# V4-AddRS485-V01-017.net
KiCad netlist of a schematic drawn in EAGLE
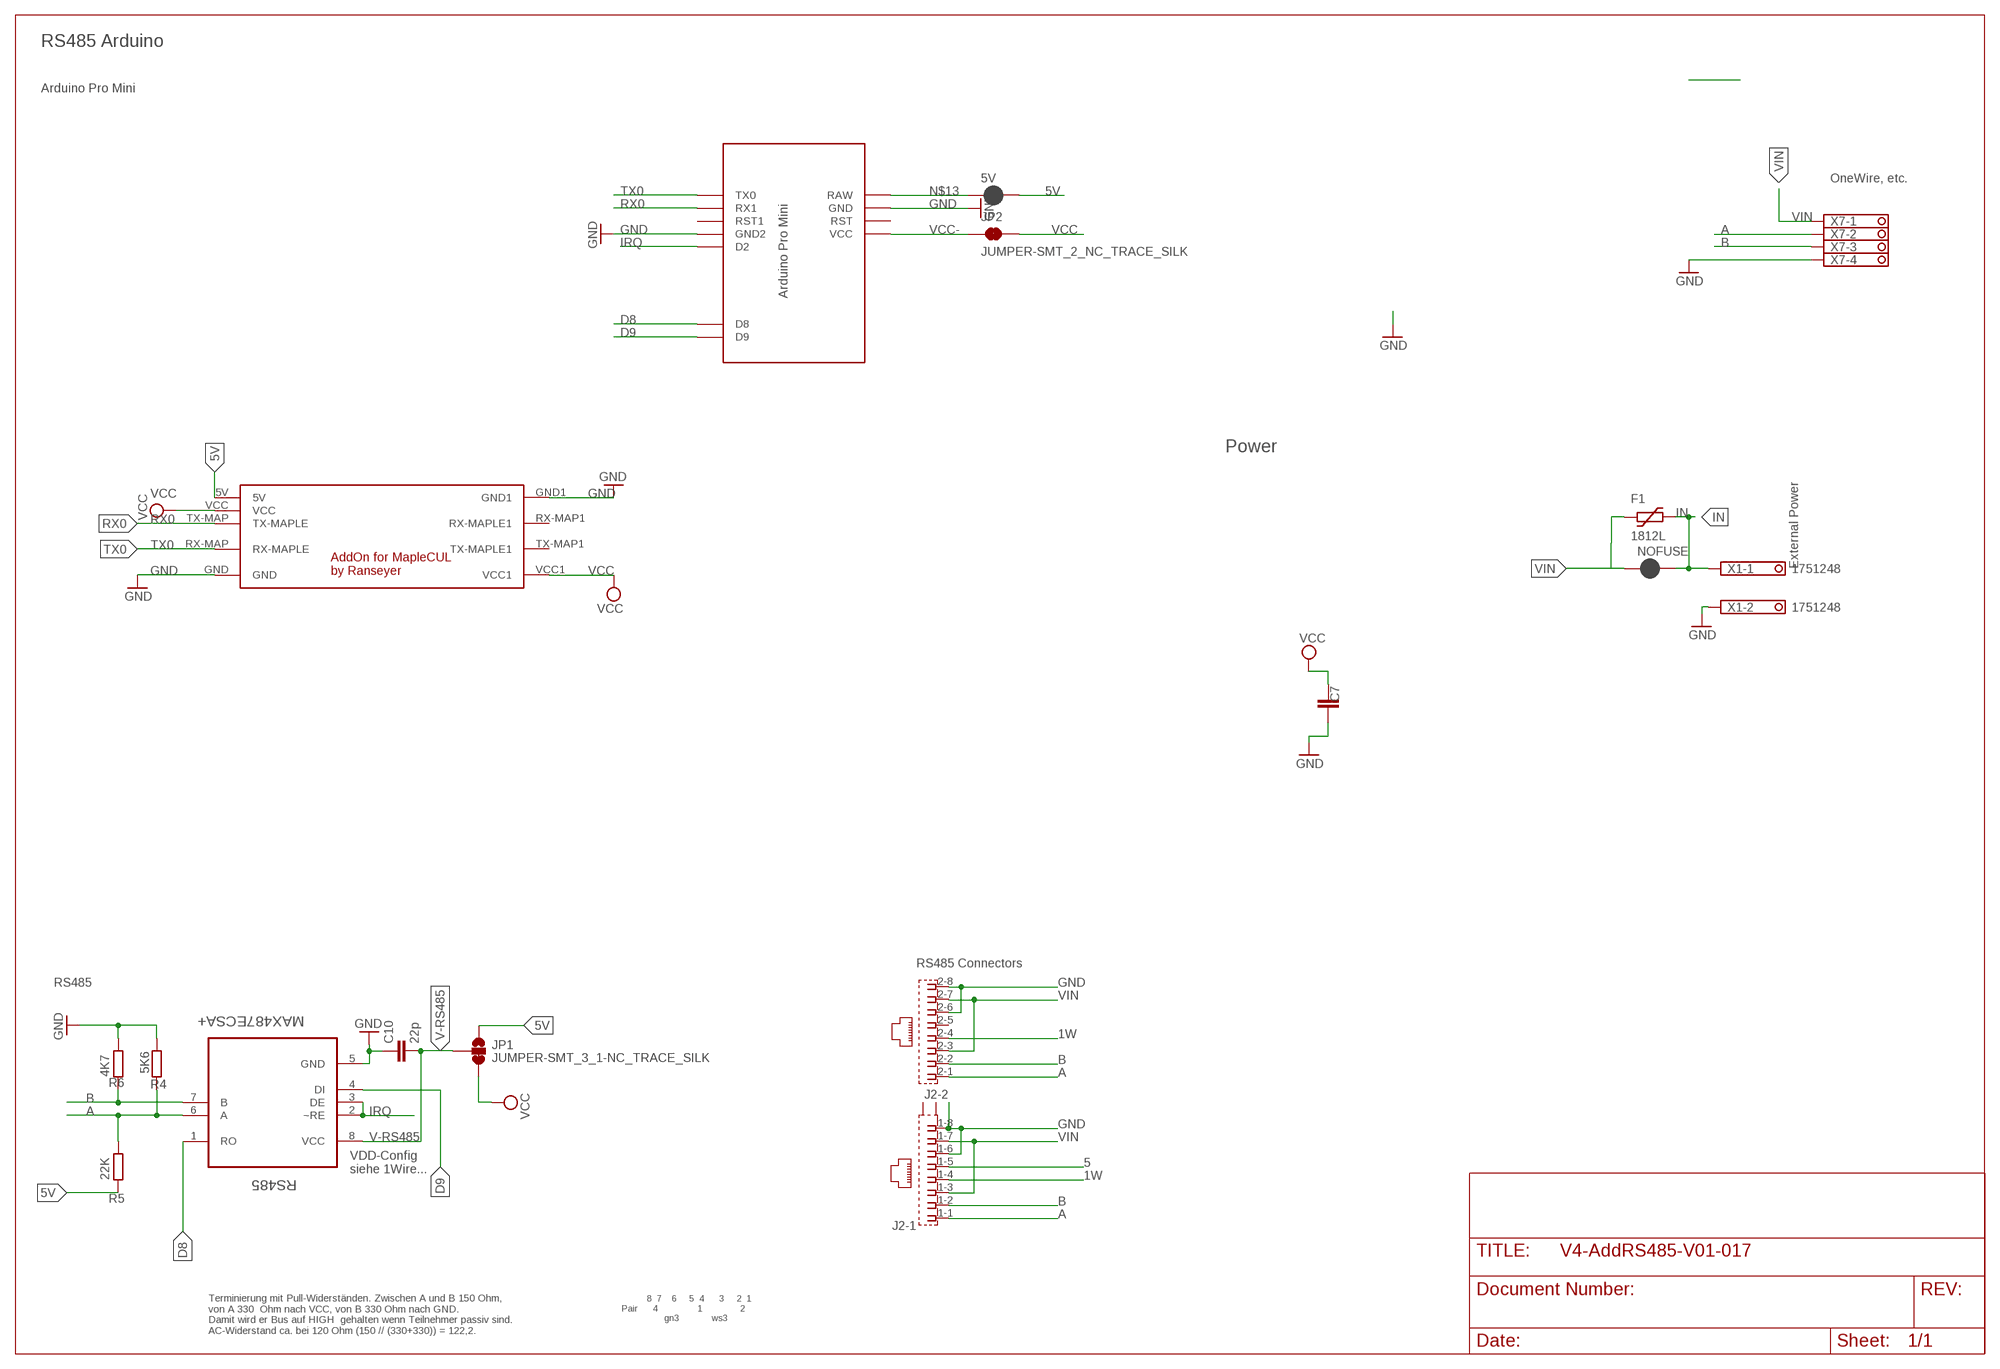
[diagram p0: schematic, sheet 1]

(export (version "E")
  (design (tool "Eeschema 10.0.6"))
  (components
    (comp (ref "5V")
      (value "JUMPER-SMT_2_NC_PASTE_NO-SILK")
      (footprint "eagle-import:SMT-JUMPER_2_NC_PASTE_NO-SILK")
      (libsource (lib "eagle-import") (part "JUMPER-SMT_2_NC_PASTE_NO-SILK"))
    )
    (comp (ref "C7")
      (value "C-EUC1812")
      (footprint "eagle-import:C1812")
      (libsource (lib "eagle-import") (part "rcl_334_C-EUC1812"))
    )
    (comp (ref "C10")
      (value "22p")
      (footprint "eagle-import:C0805")
      (libsource (lib "eagle-import") (part "C-EUC0805"))
    )
    (comp (ref "F1")
      (value "1812L")
      (footprint "eagle-import:1812L")
      (libsource (lib "eagle-import") (part "1812L"))
    )
    (comp (ref "J2")
      (value "RJ45_2X_S")
      (footprint "eagle-import:RJ45_2X_S")
      (libsource (lib "eagle-import") (part "RJ45_2X_S"))
    )
    (comp (ref "JP1")
      (value "JUMPER-SMT_3_1-NC_TRACE_SILK")
      (footprint "eagle-import:SMT-JUMPER_3_1-NC_TRACE_SILK")
      (libsource (lib "eagle-import") (part "JUMPER-SMT_3_1-NC_TRACE_SILK"))
    )
    (comp (ref "JP2")
      (value "JUMPER-SMT_2_NC_TRACE_SILK")
      (footprint "eagle-import:SMT-JUMPER_2_NC_TRACE_SILK")
      (libsource (lib "eagle-import") (part "JUMPER-SMT_2_NC_TRACE_SILK"))
    )
    (comp (ref "NOFUSE")
      (value "JUMPER-SMT_2_NC_PASTE_NO-SILK")
      (footprint "eagle-import:SMT-JUMPER_2_NC_PASTE_NO-SILK")
      (libsource (lib "eagle-import") (part "JUMPER-SMT_2_NC_PASTE_NO-SILK"))
    )
    (comp (ref "R4")
      (value "5K6")
      (footprint "eagle-import:R0805")
      (libsource (lib "eagle-import") (part "R-EU_R0805"))
    )
    (comp (ref "R5")
      (value "22K")
      (footprint "eagle-import:R0805")
      (libsource (lib "eagle-import") (part "R-EU_R0805"))
    )
    (comp (ref "R6")
      (value "4K7")
      (footprint "eagle-import:R0805")
      (libsource (lib "eagle-import") (part "R-EU_R0805"))
    )
    (comp (ref "RS485")
      (value "MAX487ECSA+")
      (footprint "eagle-import:SOIC127P600X175-8N")
      (libsource (lib "eagle-import") (part "MAX487ECSA+"))
    )
    (comp (ref "U$2")
      (value "MAPLE-CUL-ADDON-V01")
      (footprint "eagle-import:MAPLE-CUL-V01")
      (libsource (lib "eagle-import") (part "MAPLE-CUL-ADDON-V01"))
    )
    (comp (ref "U$3")
      (value "MARTIN-PRO-MINI-RS485")
      (footprint "eagle-import:MARTIN-PRO-MINI-RS485")
      (libsource (lib "eagle-import") (part "MARTIN-PRO-MINI-RS485"))
    )
    (comp (ref "X1")
      (value "1751248")
      (footprint "eagle-import:1751248")
      (libsource (lib "eagle-import") (part "1751248"))
    )
    (comp (ref "X7")
      (value "1751264")
      (footprint "eagle-import:1751264")
      (libsource (lib "eagle-import") (part "1751264"))
    )
  )
  (nets
    (net (code "1") (name "/1W") (class "Default")
      (node (ref "J2") (pin "1-4") (pinfunction "4_1-4") (pintype "passive"))
      (node (ref "J2") (pin "2-4") (pinfunction "4_2-4") (pintype "passive"))
    )
    (net (code "2") (name "/5") (class "Default")
      (node (ref "J2") (pin "1-5") (pinfunction "5_1-5") (pintype "passive"))
    )
    (net (code "3") (name "/A") (class "Default")
      (node (ref "J2") (pin "1-1") (pinfunction "1_1-1") (pintype "passive"))
      (node (ref "J2") (pin "2-1") (pinfunction "1_2-1") (pintype "passive"))
      (node (ref "R4") (pin "2") (pinfunction "2_2") (pintype "passive"))
      (node (ref "R5") (pin "2") (pinfunction "2_2") (pintype "passive"))
      (node (ref "RS485") (pin "6") (pinfunction "A_6") (pintype "bidirectional"))
      (node (ref "X7") (pin "2") (pinfunction "K_2") (pintype "passive"))
    )
    (net (code "4") (name "/B") (class "Default")
      (node (ref "J2") (pin "1-2") (pinfunction "2_1-2") (pintype "passive"))
      (node (ref "J2") (pin "2-2") (pinfunction "2_2-2") (pintype "passive"))
      (node (ref "R6") (pin "1") (pinfunction "1_1") (pintype "passive"))
      (node (ref "RS485") (pin "7") (pinfunction "B_7") (pintype "bidirectional"))
      (node (ref "X7") (pin "3") (pinfunction "K_3") (pintype "passive"))
    )
    (net (code "5") (name "/IRQ") (class "Default")
      (node (ref "RS485") (pin "2") (pinfunction "~{RE}_2") (pintype "input"))
      (node (ref "RS485") (pin "3") (pinfunction "DE_3") (pintype "input"))
      (node (ref "U$3") (pin "D2") (pinfunction "D2_D2") (pintype "bidirectional"))
    )
    (net (code "6") (name "/N$13") (class "Default")
      (node (ref "5V") (pin "1") (pinfunction "1_1") (pintype "passive"))
      (node (ref "U$3") (pin "RAW") (pinfunction "RAW_RAW") (pintype "bidirectional"))
    )
    (net (code "7") (name "/VCC-") (class "Default")
      (node (ref "JP2") (pin "1") (pinfunction "1_1") (pintype "passive"))
      (node (ref "U$3") (pin "VCC") (pinfunction "VCC_VCC") (pintype "bidirectional"))
    )
    (net (code "8") (name "5V") (class "Default")
      (node (ref "5V") (pin "2") (pinfunction "2_2") (pintype "passive"))
      (node (ref "JP1") (pin "1") (pinfunction "1_1") (pintype "passive"))
      (node (ref "R5") (pin "1") (pinfunction "1_1") (pintype "passive"))
      (node (ref "U$2") (pin "5V") (pinfunction "5V_5V") (pintype "bidirectional"))
    )
    (net (code "9") (name "D8") (class "Default")
      (node (ref "RS485") (pin "1") (pinfunction "RO_1") (pintype "output"))
      (node (ref "U$3") (pin "D8") (pinfunction "D8_D8") (pintype "bidirectional"))
    )
    (net (code "10") (name "D9") (class "Default")
      (node (ref "RS485") (pin "4") (pinfunction "DI_4") (pintype "input"))
      (node (ref "U$3") (pin "D9") (pinfunction "D9_D9") (pintype "bidirectional"))
    )
    (net (code "11") (name "GND") (class "Default")
      (node (ref "C10") (pin "1") (pinfunction "1_1") (pintype "passive"))
      (node (ref "C7") (pin "1") (pinfunction "1_1") (pintype "passive"))
      (node (ref "J2") (pin "1-6") (pinfunction "6_1-6") (pintype "passive"))
      (node (ref "J2") (pin "1-8") (pinfunction "8_1-8") (pintype "passive"))
      (node (ref "J2") (pin "2-6") (pinfunction "6_2-6") (pintype "passive"))
      (node (ref "J2") (pin "2-8") (pinfunction "8_2-8") (pintype "passive"))
      (node (ref "R4") (pin "1") (pinfunction "1_1") (pintype "passive"))
      (node (ref "R6") (pin "2") (pinfunction "2_2") (pintype "passive"))
      (node (ref "RS485") (pin "5") (pinfunction "GND_5") (pintype "passive"))
      (node (ref "U$2") (pin "GND") (pinfunction "GND_GND") (pintype "bidirectional"))
      (node (ref "U$2") (pin "GND1") (pinfunction "GND1_GND1") (pintype "bidirectional"))
      (node (ref "U$3") (pin "GND") (pinfunction "GND_GND") (pintype "bidirectional"))
      (node (ref "U$3") (pin "GND1") (pinfunction "GND2_GND1") (pintype "bidirectional"))
      (node (ref "X1") (pin "2") (pinfunction "K_2") (pintype "passive"))
      (node (ref "X7") (pin "4") (pinfunction "K_4") (pintype "passive"))
    )
    (net (code "12") (name "IN") (class "Default")
      (node (ref "F1") (pin "P$2") (pinfunction "2_P$2") (pintype "passive"))
      (node (ref "NOFUSE") (pin "2") (pinfunction "2_2") (pintype "passive"))
      (node (ref "X1") (pin "1") (pinfunction "K_1") (pintype "passive"))
    )
    (net (code "13") (name "RX0") (class "Default")
      (node (ref "U$2") (pin "TX-MAP") (pinfunction "TX-MAPLE_TX-MAP") (pintype "bidirectional"))
      (node (ref "U$3") (pin "RX1") (pinfunction "RX1_RX1") (pintype "bidirectional"))
    )
    (net (code "14") (name "TX0") (class "Default")
      (node (ref "U$2") (pin "RX-MAP") (pinfunction "RX-MAPLE_RX-MAP") (pintype "bidirectional"))
      (node (ref "U$3") (pin "TX0") (pinfunction "TX0_TX0") (pintype "bidirectional"))
    )
    (net (code "15") (name "V-RS485") (class "Default")
      (node (ref "C10") (pin "2") (pinfunction "2_2") (pintype "passive"))
      (node (ref "JP1") (pin "2") (pinfunction "2_2") (pintype "passive"))
      (node (ref "RS485") (pin "8") (pinfunction "VCC_8") (pintype "power_in"))
    )
    (net (code "16") (name "VCC") (class "Default")
      (node (ref "C7") (pin "2") (pinfunction "2_2") (pintype "passive"))
      (node (ref "JP1") (pin "3") (pinfunction "3_3") (pintype "passive"))
      (node (ref "JP2") (pin "2") (pinfunction "2_2") (pintype "passive"))
      (node (ref "U$2") (pin "VCC") (pinfunction "VCC_VCC") (pintype "bidirectional"))
      (node (ref "U$2") (pin "VCC1") (pinfunction "VCC1_VCC1") (pintype "bidirectional"))
    )
    (net (code "17") (name "VIN") (class "Default")
      (node (ref "F1") (pin "P$1") (pinfunction "1_P$1") (pintype "passive"))
      (node (ref "J2") (pin "1-3") (pinfunction "3_1-3") (pintype "passive"))
      (node (ref "J2") (pin "1-7") (pinfunction "7_1-7") (pintype "passive"))
      (node (ref "J2") (pin "2-3") (pinfunction "3_2-3") (pintype "passive"))
      (node (ref "J2") (pin "2-7") (pinfunction "7_2-7") (pintype "passive"))
      (node (ref "NOFUSE") (pin "1") (pinfunction "1_1") (pintype "passive"))
      (node (ref "X7") (pin "1") (pinfunction "K_1") (pintype "passive"))
    )
    (net (code "18") (name "unconnected-(J2A-S1-PadG3)") (class "Default")
      (node (ref "J2") (pin "G3") (pinfunction "S1_G3") (pintype "passive"))
    )
    (net (code "19") (name "unconnected-(J2A-S2-PadG1)") (class "Default")
      (node (ref "J2") (pin "G1") (pinfunction "S2_G1") (pintype "passive"))
    )
    (net (code "20") (name "unconnected-(J2B-5-Pad2-5)") (class "Default")
      (node (ref "J2") (pin "2-5") (pinfunction "5_2-5") (pintype "passive"))
    )
    (net (code "21") (name "unconnected-(U$2-RX-MAPLE1-PadRX-MAP1)") (class "Default")
      (node (ref "U$2") (pin "RX-MAP1") (pinfunction "RX-MAPLE1_RX-MAP1") (pintype "bidirectional"))
    )
    (net (code "22") (name "unconnected-(U$2-TX-MAPLE1-PadTX-MAP1)") (class "Default")
      (node (ref "U$2") (pin "TX-MAP1") (pinfunction "TX-MAPLE1_TX-MAP1") (pintype "bidirectional"))
    )
    (net (code "23") (name "unconnected-(U$3-PadRST)") (class "Default")
      (node (ref "U$3") (pin "RST") (pinfunction "RST_RST") (pintype "bidirectional"))
    )
    (net (code "24") (name "unconnected-(U$3-PadRST1)") (class "Default")
      (node (ref "U$3") (pin "RST1") (pinfunction "RST1_RST1") (pintype "bidirectional"))
    )
  )
)
